# Sheet1.net
KiCad netlist of a schematic drawn in Altium Designer
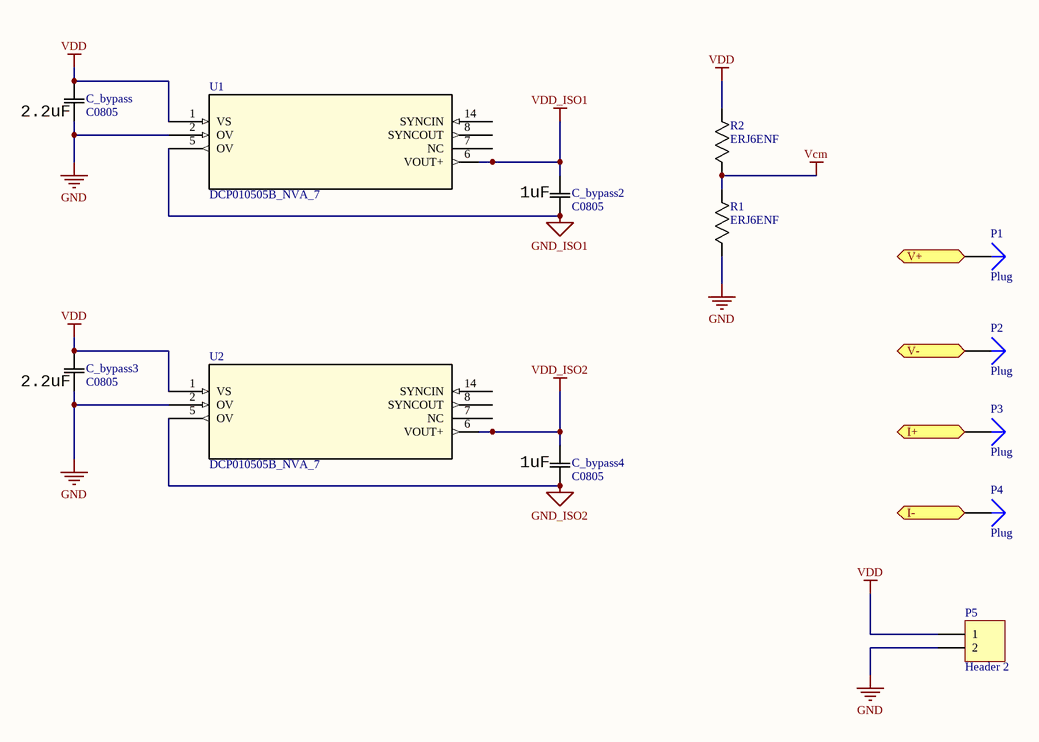
[diagram p0: Sheet1.SchDoc]

(export (version "E")
  (design (tool "Eeschema 10.0.6"))
  (components
    (comp (ref "C_bypass")
      (value "C0805")
      (footprint "C0805C")
      (description "Imported")
      (fields
        (field (name "MANUFACTURER_PART_NUMBER") "C0805C100C1GACTU")
        (field (name "ALTIUM_VALUE") "2.2uF")
      )
      (libsource (lib "C0805") (part "C0805"))
    )
    (comp (ref "C_bypass2")
      (value "C0805")
      (footprint "C0805C")
      (description "Imported")
      (fields
        (field (name "MANUFACTURER_PART_NUMBER") "C0805C100C1GACTU")
        (field (name "ALTIUM_VALUE") "1uF")
      )
      (libsource (lib "C0805") (part "C0805"))
    )
    (comp (ref "C_bypass3")
      (value "C0805")
      (footprint "C0805C")
      (description "Imported")
      (fields
        (field (name "MANUFACTURER_PART_NUMBER") "C0805C100C1GACTU")
        (field (name "ALTIUM_VALUE") "2.2uF")
      )
      (libsource (lib "C0805") (part "C0805"))
    )
    (comp (ref "C_bypass4")
      (value "C0805")
      (footprint "C0805C")
      (description "Imported")
      (fields
        (field (name "MANUFACTURER_PART_NUMBER") "C0805C100C1GACTU")
        (field (name "ALTIUM_VALUE") "1uF")
      )
      (libsource (lib "C0805") (part "C0805"))
    )
    (comp (ref "P1")
      (value "Plug")
      (footprint "PIN1")
      (fields (field (name "PUBLISHER") "Altium Limited"))
      (libsource (lib "Miscellaneous Connectors") (part "Plug"))
    )
    (comp (ref "P2")
      (value "Plug")
      (footprint "PIN1")
      (fields (field (name "PUBLISHER") "Altium Limited"))
      (libsource (lib "Miscellaneous Connectors") (part "Plug"))
    )
    (comp (ref "P3")
      (value "Plug")
      (footprint "PIN1")
      (fields (field (name "PUBLISHER") "Altium Limited"))
      (libsource (lib "Miscellaneous Connectors") (part "Plug"))
    )
    (comp (ref "P4")
      (value "Plug")
      (footprint "PIN1")
      (fields (field (name "PUBLISHER") "Altium Limited"))
      (libsource (lib "Miscellaneous Connectors") (part "Plug"))
    )
    (comp (ref "P5")
      (value "Header 2")
      (footprint "HDR1X2")
      (description "Header, 2-Pin")
      (fields (field (name "PUBLISHER") "Altium Limited"))
      (libsource (lib "Miscellaneous Connectors") (part "Header 2"))
    )
    (comp (ref "R1")
      (value "ERJ6ENF")
      (footprint "0805")
      (description "Imported")
      (fields (field (name "MANUFACTURER_PART_NUMBER") "ERJ6ENF1000V"))
      (libsource (lib "ERJ6EN_125mW") (part "ERJ6ENF"))
    )
    (comp (ref "R2")
      (value "ERJ6ENF")
      (footprint "0805")
      (description "Imported")
      (fields (field (name "MANUFACTURER_PART_NUMBER") "ERJ6ENF1000V"))
      (libsource (lib "ERJ6EN_125mW") (part "ERJ6ENF"))
    )
    (comp (ref "U1")
      (value "DCP010505B_NVA_7")
      (footprint "NVA7")
      (description "Imported")
      (fields (field (name "MANUFACTURER") "Texas Instruments"))
      (libsource (lib "DCP0105B_NVA") (part "DCP010505B_NVA_7"))
    )
    (comp (ref "U2")
      (value "DCP010505B_NVA_7")
      (footprint "NVA7")
      (description "Imported")
      (fields (field (name "MANUFACTURER") "Texas Instruments"))
      (libsource (lib "DCP0105B_NVA") (part "DCP010505B_NVA_7"))
    )
  )
  (nets
    (net (code "1") (name "/I+") (class "Default")
      (node (ref "P3") (pin "1") (pinfunction "1_1") (pintype "passive"))
    )
    (net (code "2") (name "/I-") (class "Default")
      (node (ref "P4") (pin "1") (pinfunction "1_1") (pintype "passive"))
    )
    (net (code "3") (name "/V+") (class "Default")
      (node (ref "P1") (pin "1") (pinfunction "1_1") (pintype "passive"))
    )
    (net (code "4") (name "/V-") (class "Default")
      (node (ref "P2") (pin "1") (pinfunction "1_1") (pintype "passive"))
    )
    (net (code "5") (name "GND") (class "Default")
      (node (ref "C_bypass") (pin "2") (pinfunction "2_2") (pintype "passive"))
      (node (ref "C_bypass3") (pin "2") (pinfunction "2_2") (pintype "passive"))
      (node (ref "P5") (pin "2") (pinfunction "2_2") (pintype "passive"))
      (node (ref "R1") (pin "1") (pinfunction "1_1") (pintype "passive"))
      (node (ref "U1") (pin "2") (pinfunction "OV_2") (pintype "input"))
      (node (ref "U2") (pin "2") (pinfunction "OV_2") (pintype "input"))
    )
    (net (code "6") (name "GND_ISO1") (class "Default")
      (node (ref "C_bypass2") (pin "2") (pinfunction "2_2") (pintype "passive"))
      (node (ref "U1") (pin "5") (pinfunction "OV_5") (pintype "output"))
    )
    (net (code "7") (name "GND_ISO2") (class "Default")
      (node (ref "C_bypass4") (pin "2") (pinfunction "2_2") (pintype "passive"))
      (node (ref "U2") (pin "5") (pinfunction "OV_5") (pintype "output"))
    )
    (net (code "8") (name "VDD") (class "Default")
      (node (ref "C_bypass") (pin "1") (pinfunction "1_1") (pintype "passive"))
      (node (ref "C_bypass3") (pin "1") (pinfunction "1_1") (pintype "passive"))
      (node (ref "P5") (pin "1") (pinfunction "1_1") (pintype "passive"))
      (node (ref "R2") (pin "2") (pinfunction "2_2") (pintype "passive"))
      (node (ref "U1") (pin "1") (pinfunction "VS_1") (pintype "input"))
      (node (ref "U2") (pin "1") (pinfunction "VS_1") (pintype "input"))
    )
    (net (code "9") (name "VDD_ISO1") (class "Default")
      (node (ref "C_bypass2") (pin "1") (pinfunction "1_1") (pintype "passive"))
      (node (ref "U1") (pin "6") (pinfunction "VOUT+_6") (pintype "output"))
    )
    (net (code "10") (name "VDD_ISO2") (class "Default")
      (node (ref "C_bypass4") (pin "1") (pinfunction "1_1") (pintype "passive"))
      (node (ref "U2") (pin "6") (pinfunction "VOUT+_6") (pintype "output"))
    )
    (net (code "11") (name "Vcm") (class "Default")
      (node (ref "R1") (pin "2") (pinfunction "2_2") (pintype "passive"))
      (node (ref "R2") (pin "1") (pinfunction "1_1") (pintype "passive"))
    )
    (net (code "12") (name "unconnected-(U1-NC-Pad7)") (class "Default")
      (node (ref "U1") (pin "7") (pinfunction "NC_7") (pintype "passive"))
    )
    (net (code "13") (name "unconnected-(U1-SYNCIN-Pad14)") (class "Default")
      (node (ref "U1") (pin "14") (pinfunction "SYNCIN_14") (pintype "input"))
    )
    (net (code "14") (name "unconnected-(U1-SYNCOUT-Pad8)") (class "Default")
      (node (ref "U1") (pin "8") (pinfunction "SYNCOUT_8") (pintype "output"))
    )
    (net (code "15") (name "unconnected-(U2-NC-Pad7)") (class "Default")
      (node (ref "U2") (pin "7") (pinfunction "NC_7") (pintype "passive"))
    )
    (net (code "16") (name "unconnected-(U2-SYNCIN-Pad14)") (class "Default")
      (node (ref "U2") (pin "14") (pinfunction "SYNCIN_14") (pintype "input"))
    )
    (net (code "17") (name "unconnected-(U2-SYNCOUT-Pad8)") (class "Default")
      (node (ref "U2") (pin "8") (pinfunction "SYNCOUT_8") (pintype "output"))
    )
  )
)
